# PM3_Bosclone_MCU_2.net
KiCad netlist of a schematic drawn in Altium Designer
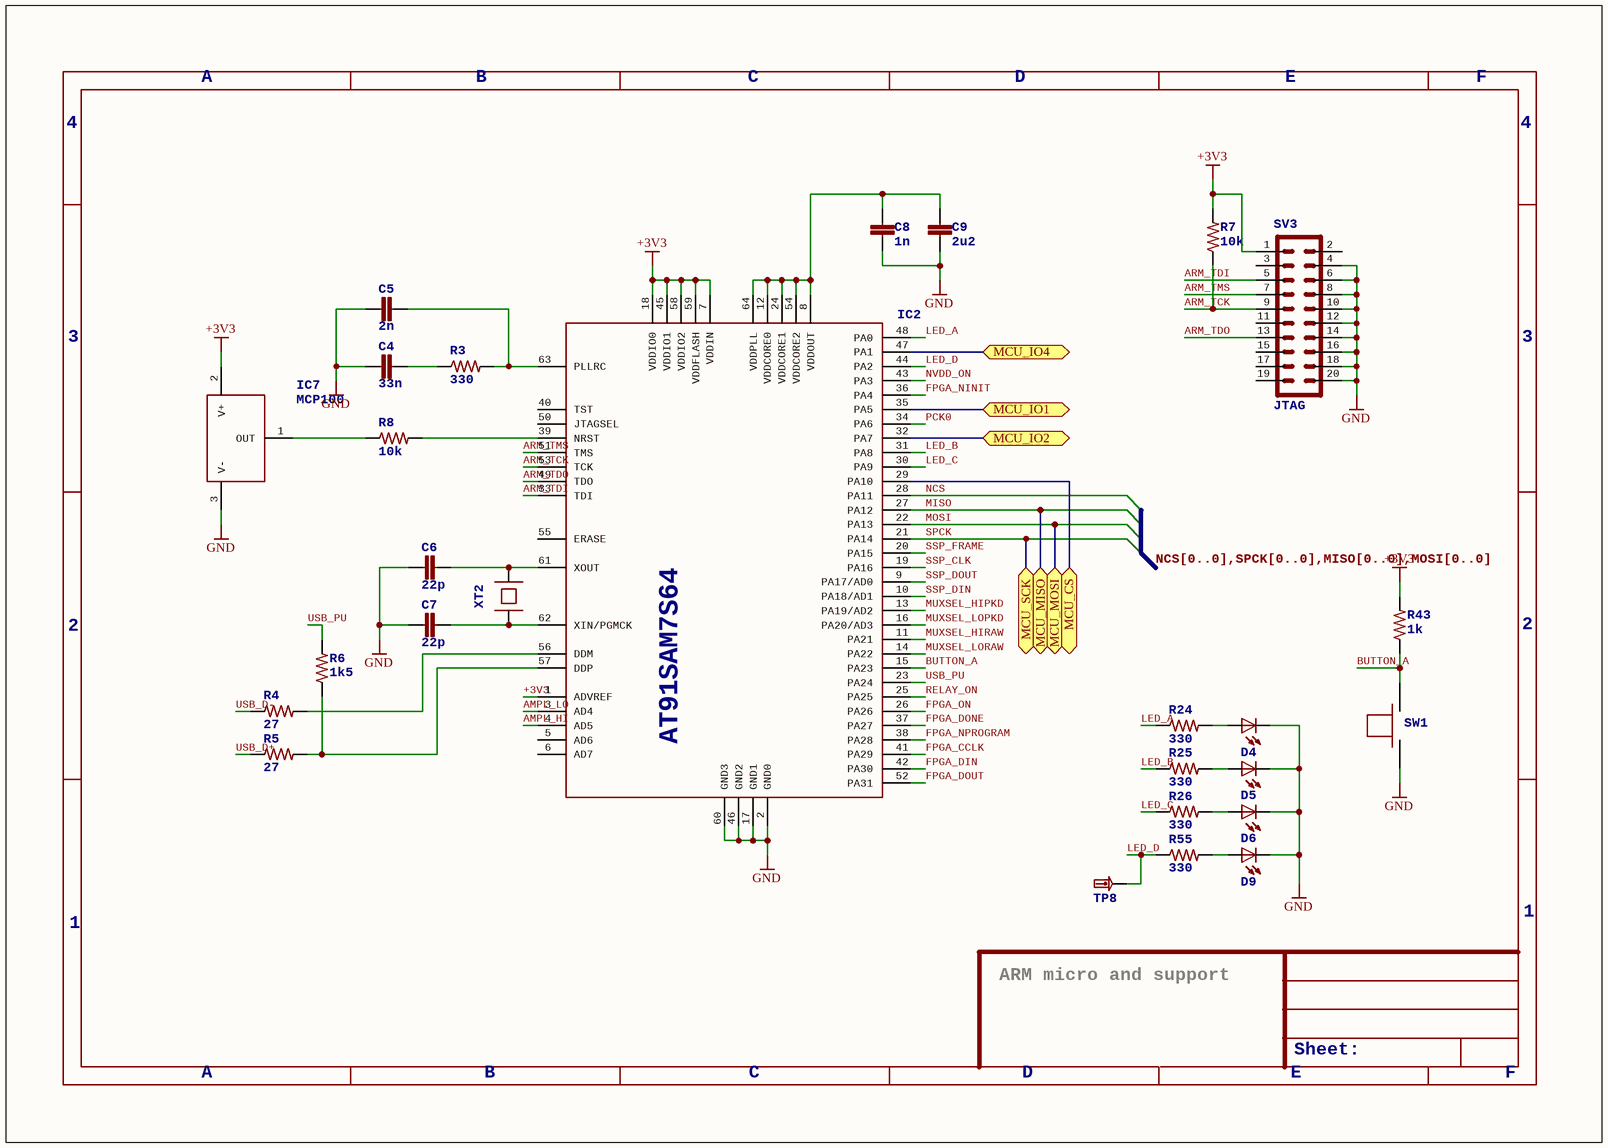
[diagram p0: PM3_Bosclone_MCU_2.SchDoc]

(export (version "E")
  (design (tool "Eeschema 10.0.6"))
  (components
    (comp (ref "C4") (value "33n") (footprint "RLC_0603") (libsource (lib "merged") (part "CAPACITOR0603")))
    (comp (ref "C5") (value "2n") (footprint "RLC_0603") (libsource (lib "merged") (part "CAPACITOR0603")))
    (comp (ref "C6") (value "22p") (footprint "RLC_0603") (libsource (lib "merged") (part "CAPACITOR0603")))
    (comp (ref "C7") (value "22p") (footprint "RLC_0603") (libsource (lib "merged") (part "CAPACITOR0603")))
    (comp (ref "C8") (value "1n") (footprint "RLC_0603") (libsource (lib "") (part "CAPACITOR0603_1")))
    (comp (ref "C9") (value "2u2") (footprint "RLC_1210") (libsource (lib "merged") (part "CAPACITOR1210")))
    (comp (ref "D4") (value "LED") (footprint "LED_0603") (libsource (lib "merged") (part "LED")))
    (comp (ref "D5") (value "LED") (footprint "LED_0603") (libsource (lib "merged") (part "LED")))
    (comp (ref "D6") (value "LED") (footprint "LED_0603") (libsource (lib "merged") (part "LED")))
    (comp (ref "D9") (value "LED") (footprint "LED_0603") (libsource (lib "merged") (part "LED")))
    (comp (ref "IC2")
      (value "AT91SAM7S64")
      (footprint "LQFP-64")
      (fields (field (name "AT91SAM7S64") "AT91SAM7S64"))
      (libsource (lib "merged") (part "AT91SAM7S64"))
    )
    (comp (ref "IC7") (value "MCP100") (footprint "SOT23-3LEAD") (libsource (lib "merged") (part "MCP100")))
    (comp (ref "R3") (value "330") (footprint "RLC_0603") (libsource (lib "merged") (part "RESISTOR0603")))
    (comp (ref "R4") (value "27") (footprint "RLC_0603") (libsource (lib "merged") (part "RESISTOR0603")))
    (comp (ref "R5") (value "27") (footprint "RLC_0603") (libsource (lib "merged") (part "RESISTOR0603")))
    (comp (ref "R6") (value "1k5") (footprint "RLC_0603") (libsource (lib "merged") (part "RESISTOR0603")))
    (comp (ref "R7") (value "10k") (footprint "RLC_0603") (libsource (lib "merged") (part "RESISTOR0603")))
    (comp (ref "R8") (value "10k") (footprint "RLC_0603") (libsource (lib "merged") (part "RESISTOR0603")))
    (comp (ref "R24") (value "330") (footprint "RLC_0603") (libsource (lib "merged") (part "RESISTOR0603")))
    (comp (ref "R25") (value "330") (footprint "RLC_0603") (libsource (lib "merged") (part "RESISTOR0603")))
    (comp (ref "R26") (value "330") (footprint "RLC_0603") (libsource (lib "merged") (part "RESISTOR0603")))
    (comp (ref "R43") (value "1k") (footprint "RLC_0603") (libsource (lib "merged") (part "RESISTOR0603")))
    (comp (ref "R55") (value "330") (footprint "RLC_0603") (libsource (lib "merged") (part "RESISTOR0603")))
    (comp (ref "SV3")
      (value "JTAG")
      (footprint "HEADER-MALE-10X2-0.100-SHROUDED")
      (libsource (lib "merged") (part "HEADER-MALE-10X2"))
    )
    (comp (ref "SW1")
      (value "TACTSWITCH")
      (footprint "TACTSWITCH-SMD-EVQQ1")
      (libsource (lib "merged") (part "TACTSWITCH"))
    )
    (comp (ref "TP8")
      (value "TESTPADKEYSTONE-SMD")
      (footprint "KEYSTONE-SMD-TESTPOINT-5015")
      (libsource (lib "merged") (part "TESTPADKEYSTONE-SMD"))
    )
    (comp (ref "XT2")
      (value "XTAL-SMD-CITIZEN-CS10")
      (footprint "XTAL-SMD-CITIZEN-CS10")
      (libsource (lib "merged") (part "XTAL-SMD-CITIZEN-CS10"))
    )
  )
  (nets
    (net (code "2") (name "+3V3") (class "Default")
      (node (ref "IC2") (pin "1") (pinfunction "ADVREF_1") (pintype "passive"))
      (node (ref "IC2") (pin "18") (pinfunction "VDDIO0_18") (pintype "passive"))
      (node (ref "IC2") (pin "45") (pinfunction "VDDIO1_45") (pintype "passive"))
      (node (ref "IC2") (pin "58") (pinfunction "VDDIO2_58") (pintype "passive"))
      (node (ref "IC2") (pin "59") (pinfunction "VDDFLASH_59") (pintype "passive"))
      (node (ref "IC2") (pin "7") (pinfunction "VDDIN_7") (pintype "passive"))
      (node (ref "IC7") (pin "2") (pinfunction "V+_2") (pintype "passive"))
      (node (ref "R43") (pin "2") (pinfunction "2_2") (pintype "passive"))
      (node (ref "R7") (pin "2") (pinfunction "2_2") (pintype "passive"))
      (node (ref "SV3") (pin "1") (pinfunction "1_1") (pintype "passive"))
    )
    (net (code "3") (name "/AMPL_HI") (class "Default")
      (node (ref "IC2") (pin "4") (pinfunction "AD5_4") (pintype "passive"))
    )
    (net (code "4") (name "/AMPL_LO") (class "Default")
      (node (ref "IC2") (pin "3") (pinfunction "AD4_3") (pintype "passive"))
    )
    (net (code "5") (name "/ARM_TCK") (class "Default")
      (node (ref "IC2") (pin "53") (pinfunction "TCK_53") (pintype "passive"))
      (node (ref "R7") (pin "1") (pinfunction "1_1") (pintype "passive"))
      (node (ref "SV3") (pin "9") (pinfunction "9_9") (pintype "passive"))
    )
    (net (code "6") (name "/ARM_TDI") (class "Default")
      (node (ref "IC2") (pin "33") (pinfunction "TDI_33") (pintype "passive"))
      (node (ref "SV3") (pin "5") (pinfunction "5_5") (pintype "passive"))
    )
    (net (code "7") (name "/ARM_TDO") (class "Default")
      (node (ref "IC2") (pin "49") (pinfunction "TDO_49") (pintype "passive"))
      (node (ref "SV3") (pin "13") (pinfunction "13_13") (pintype "passive"))
    )
    (net (code "8") (name "/ARM_TMS") (class "Default")
      (node (ref "IC2") (pin "51") (pinfunction "TMS_51") (pintype "passive"))
      (node (ref "SV3") (pin "7") (pinfunction "7_7") (pintype "passive"))
    )
    (net (code "9") (name "/BUTTON_A") (class "Default")
      (node (ref "IC2") (pin "15") (pinfunction "PA23_15") (pintype "passive"))
      (node (ref "R43") (pin "1") (pinfunction "1_1") (pintype "passive"))
      (node (ref "SW1") (pin "B") (pinfunction "P$2_B") (pintype "passive"))
    )
    (net (code "10") (name "/FPGA_CCLK") (class "Default")
      (node (ref "IC2") (pin "41") (pinfunction "PA29_41") (pintype "passive"))
    )
    (net (code "11") (name "/FPGA_DIN") (class "Default")
      (node (ref "IC2") (pin "42") (pinfunction "PA30_42") (pintype "passive"))
    )
    (net (code "12") (name "/FPGA_DONE") (class "Default")
      (node (ref "IC2") (pin "37") (pinfunction "PA27_37") (pintype "passive"))
    )
    (net (code "13") (name "/FPGA_DOUT") (class "Default")
      (node (ref "IC2") (pin "52") (pinfunction "PA31_52") (pintype "passive"))
    )
    (net (code "14") (name "/FPGA_NINIT") (class "Default")
      (node (ref "IC2") (pin "36") (pinfunction "PA4_36") (pintype "passive"))
    )
    (net (code "15") (name "/FPGA_NPROGRAM") (class "Default")
      (node (ref "IC2") (pin "38") (pinfunction "PA28_38") (pintype "passive"))
    )
    (net (code "16") (name "/FPGA_ON") (class "Default")
      (node (ref "IC2") (pin "26") (pinfunction "PA26_26") (pintype "passive"))
    )
    (net (code "17") (name "/LED_A") (class "Default")
      (node (ref "IC2") (pin "48") (pinfunction "PA0_48") (pintype "passive"))
      (node (ref "R24") (pin "1") (pinfunction "1_1") (pintype "passive"))
    )
    (net (code "18") (name "/LED_B") (class "Default")
      (node (ref "IC2") (pin "31") (pinfunction "PA8_31") (pintype "passive"))
      (node (ref "R25") (pin "1") (pinfunction "1_1") (pintype "passive"))
    )
    (net (code "19") (name "/LED_C") (class "Default")
      (node (ref "IC2") (pin "30") (pinfunction "PA9_30") (pintype "passive"))
      (node (ref "R26") (pin "1") (pinfunction "1_1") (pintype "passive"))
    )
    (net (code "20") (name "/LED_D") (class "Default")
      (node (ref "IC2") (pin "44") (pinfunction "PA2_44") (pintype "passive"))
      (node (ref "R55") (pin "1") (pinfunction "1_1") (pintype "passive"))
      (node (ref "TP8") (pin "1") (pinfunction "P$1_1") (pintype "passive"))
    )
    (net (code "21") (name "/MCU_CS") (class "Default")
      (node (ref "IC2") (pin "29") (pinfunction "PA10_29") (pintype "passive"))
    )
    (net (code "22") (name "/MCU_IO1") (class "Default")
      (node (ref "IC2") (pin "35") (pinfunction "PA5_35") (pintype "passive"))
    )
    (net (code "23") (name "/MCU_IO2") (class "Default")
      (node (ref "IC2") (pin "32") (pinfunction "PA7_32") (pintype "passive"))
    )
    (net (code "24") (name "/MCU_IO4") (class "Default")
      (node (ref "IC2") (pin "47") (pinfunction "PA1_47") (pintype "passive"))
    )
    (net (code "25") (name "/MISO") (class "Default")
      (node (ref "IC2") (pin "27") (pinfunction "PA12_27") (pintype "passive"))
    )
    (net (code "26") (name "/MOSI") (class "Default")
      (node (ref "IC2") (pin "22") (pinfunction "PA13_22") (pintype "passive"))
    )
    (net (code "27") (name "/MUXSEL_HIPKD") (class "Default")
      (node (ref "IC2") (pin "13") (pinfunction "PA19/AD2_13") (pintype "passive"))
    )
    (net (code "28") (name "/MUXSEL_HIRAW") (class "Default")
      (node (ref "IC2") (pin "11") (pinfunction "PA21_11") (pintype "passive"))
    )
    (net (code "29") (name "/MUXSEL_LOPKD") (class "Default")
      (node (ref "IC2") (pin "16") (pinfunction "PA20/AD3_16") (pintype "passive"))
    )
    (net (code "30") (name "/MUXSEL_LORAW") (class "Default")
      (node (ref "IC2") (pin "14") (pinfunction "PA22_14") (pintype "passive"))
    )
    (net (code "31") (name "/NCS") (class "Default")
      (node (ref "IC2") (pin "28") (pinfunction "PA11_28") (pintype "passive"))
    )
    (net (code "32") (name "/NVDD_ON") (class "Default")
      (node (ref "IC2") (pin "43") (pinfunction "PA3_43") (pintype "passive"))
    )
    (net (code "33") (name "/PCK0") (class "Default")
      (node (ref "IC2") (pin "34") (pinfunction "PA6_34") (pintype "passive"))
    )
    (net (code "34") (name "/RELAY_ON") (class "Default")
      (node (ref "IC2") (pin "25") (pinfunction "PA25_25") (pintype "passive"))
    )
    (net (code "35") (name "/SPCK") (class "Default")
      (node (ref "IC2") (pin "21") (pinfunction "PA14_21") (pintype "passive"))
    )
    (net (code "36") (name "/SSP_CLK") (class "Default")
      (node (ref "IC2") (pin "19") (pinfunction "PA16_19") (pintype "passive"))
    )
    (net (code "37") (name "/SSP_DIN") (class "Default")
      (node (ref "IC2") (pin "10") (pinfunction "PA18/AD1_10") (pintype "passive"))
    )
    (net (code "38") (name "/SSP_DOUT") (class "Default")
      (node (ref "IC2") (pin "9") (pinfunction "PA17/AD0_9") (pintype "passive"))
    )
    (net (code "39") (name "/SSP_FRAME") (class "Default")
      (node (ref "IC2") (pin "20") (pinfunction "PA15_20") (pintype "passive"))
    )
    (net (code "40") (name "/USB_D+") (class "Default")
      (node (ref "R5") (pin "1") (pinfunction "1_1") (pintype "passive"))
    )
    (net (code "41") (name "/USB_D-") (class "Default")
      (node (ref "R4") (pin "1") (pinfunction "1_1") (pintype "passive"))
    )
    (net (code "42") (name "/USB_PU") (class "Default")
      (node (ref "IC2") (pin "23") (pinfunction "PA24_23") (pintype "passive"))
      (node (ref "R6") (pin "2") (pinfunction "2_2") (pintype "passive"))
    )
    (net (code "44") (name "GND") (class "Default")
      (node (ref "C4") (pin "1") (pinfunction "1_1") (pintype "passive"))
      (node (ref "C5") (pin "1") (pinfunction "1_1") (pintype "passive"))
      (node (ref "C6") (pin "1") (pinfunction "1_1") (pintype "passive"))
      (node (ref "C7") (pin "1") (pinfunction "1_1") (pintype "passive"))
      (node (ref "C8") (pin "2") (pinfunction "2_2") (pintype "passive"))
      (node (ref "C9") (pin "2") (pinfunction "2_2") (pintype "passive"))
      (node (ref "D4") (pin "-") (pinfunction "C_-") (pintype "passive"))
      (node (ref "D5") (pin "-") (pinfunction "C_-") (pintype "passive"))
      (node (ref "D6") (pin "-") (pinfunction "C_-") (pintype "passive"))
      (node (ref "D9") (pin "-") (pinfunction "C_-") (pintype "passive"))
      (node (ref "IC2") (pin "17") (pinfunction "GND1_17") (pintype "passive"))
      (node (ref "IC2") (pin "2") (pinfunction "GND0_2") (pintype "passive"))
      (node (ref "IC2") (pin "46") (pinfunction "GND2_46") (pintype "passive"))
      (node (ref "IC2") (pin "60") (pinfunction "GND3_60") (pintype "passive"))
      (node (ref "IC7") (pin "3") (pinfunction "V-_3") (pintype "passive"))
      (node (ref "SV3") (pin "10") (pinfunction "10_10") (pintype "passive"))
      (node (ref "SV3") (pin "12") (pinfunction "12_12") (pintype "passive"))
      (node (ref "SV3") (pin "14") (pinfunction "14_14") (pintype "passive"))
      (node (ref "SV3") (pin "16") (pinfunction "16_16") (pintype "passive"))
      (node (ref "SV3") (pin "18") (pinfunction "18_18") (pintype "passive"))
      (node (ref "SV3") (pin "20") (pinfunction "20_20") (pintype "passive"))
      (node (ref "SV3") (pin "4") (pinfunction "4_4") (pintype "passive"))
      (node (ref "SV3") (pin "6") (pinfunction "6_6") (pintype "passive"))
      (node (ref "SV3") (pin "8") (pinfunction "8_8") (pintype "passive"))
      (node (ref "SW1") (pin "A") (pinfunction "P$1_A") (pintype "passive"))
    )
    (net (code "45") (name "Net-(C4-Pad2)") (class "Default")
      (node (ref "C4") (pin "2") (pinfunction "2_2") (pintype "passive"))
      (node (ref "R3") (pin "1") (pinfunction "1_1") (pintype "passive"))
    )
    (net (code "46") (name "Net-(D4-A)") (class "Default")
      (node (ref "D4") (pin "+") (pinfunction "A_+") (pintype "passive"))
      (node (ref "R24") (pin "2") (pinfunction "2_2") (pintype "passive"))
    )
    (net (code "47") (name "Net-(D5-A)") (class "Default")
      (node (ref "D5") (pin "+") (pinfunction "A_+") (pintype "passive"))
      (node (ref "R25") (pin "2") (pinfunction "2_2") (pintype "passive"))
    )
    (net (code "48") (name "Net-(D6-A)") (class "Default")
      (node (ref "D6") (pin "+") (pinfunction "A_+") (pintype "passive"))
      (node (ref "R26") (pin "2") (pinfunction "2_2") (pintype "passive"))
    )
    (net (code "49") (name "Net-(D9-A)") (class "Default")
      (node (ref "D9") (pin "+") (pinfunction "A_+") (pintype "passive"))
      (node (ref "R55") (pin "2") (pinfunction "2_2") (pintype "passive"))
    )
    (net (code "50") (name "Net-(IC2-DDM)") (class "Default")
      (node (ref "IC2") (pin "56") (pinfunction "DDM_56") (pintype "passive"))
      (node (ref "R4") (pin "2") (pinfunction "2_2") (pintype "passive"))
    )
    (net (code "51") (name "Net-(IC2-DDP)") (class "Default")
      (node (ref "IC2") (pin "57") (pinfunction "DDP_57") (pintype "passive"))
      (node (ref "R5") (pin "2") (pinfunction "2_2") (pintype "passive"))
      (node (ref "R6") (pin "1") (pinfunction "1_1") (pintype "passive"))
    )
    (net (code "52") (name "Net-(IC2-NRST)") (class "Default")
      (node (ref "IC2") (pin "39") (pinfunction "NRST_39") (pintype "passive"))
      (node (ref "R8") (pin "2") (pinfunction "2_2") (pintype "passive"))
    )
    (net (code "53") (name "Net-(IC2-PLLRC)") (class "Default")
      (node (ref "C5") (pin "2") (pinfunction "2_2") (pintype "passive"))
      (node (ref "IC2") (pin "63") (pinfunction "PLLRC_63") (pintype "passive"))
      (node (ref "R3") (pin "2") (pinfunction "2_2") (pintype "passive"))
    )
    (net (code "54") (name "Net-(IC2-VDDCORE0)") (class "Default")
      (node (ref "C8") (pin "1") (pinfunction "1_1") (pintype "passive"))
      (node (ref "C9") (pin "1") (pinfunction "1_1") (pintype "passive"))
      (node (ref "IC2") (pin "12") (pinfunction "VDDCORE0_12") (pintype "passive"))
      (node (ref "IC2") (pin "24") (pinfunction "VDDCORE1_24") (pintype "passive"))
      (node (ref "IC2") (pin "54") (pinfunction "VDDCORE2_54") (pintype "passive"))
      (node (ref "IC2") (pin "64") (pinfunction "VDDPLL_64") (pintype "passive"))
      (node (ref "IC2") (pin "8") (pinfunction "VDDOUT_8") (pintype "passive"))
    )
    (net (code "55") (name "Net-(IC2-XIN{slash}PGMCK)") (class "Default")
      (node (ref "C7") (pin "2") (pinfunction "2_2") (pintype "passive"))
      (node (ref "IC2") (pin "62") (pinfunction "XIN/PGMCK_62") (pintype "passive"))
      (node (ref "XT2") (pin "A") (pinfunction "A_A") (pintype "passive"))
    )
    (net (code "56") (name "Net-(IC2-XOUT)") (class "Default")
      (node (ref "C6") (pin "2") (pinfunction "2_2") (pintype "passive"))
      (node (ref "IC2") (pin "61") (pinfunction "XOUT_61") (pintype "passive"))
      (node (ref "XT2") (pin "B") (pinfunction "B_B") (pintype "passive"))
    )
    (net (code "57") (name "Net-(IC7-OUT)") (class "Default")
      (node (ref "IC7") (pin "1") (pinfunction "OUT_1") (pintype "passive"))
      (node (ref "R8") (pin "1") (pinfunction "1_1") (pintype "passive"))
    )
    (net (code "58") (name "unconnected-(IC2-AD6-Pad5)") (class "Default")
      (node (ref "IC2") (pin "5") (pinfunction "AD6_5") (pintype "passive"))
    )
    (net (code "59") (name "unconnected-(IC2-AD7-Pad6)") (class "Default")
      (node (ref "IC2") (pin "6") (pinfunction "AD7_6") (pintype "passive"))
    )
    (net (code "60") (name "unconnected-(IC2-ERASE-Pad55)") (class "Default")
      (node (ref "IC2") (pin "55") (pinfunction "ERASE_55") (pintype "passive"))
    )
    (net (code "61") (name "unconnected-(IC2-JTAGSEL-Pad50)") (class "Default")
      (node (ref "IC2") (pin "50") (pinfunction "JTAGSEL_50") (pintype "passive"))
    )
    (net (code "62") (name "unconnected-(IC2-TST-Pad40)") (class "Default")
      (node (ref "IC2") (pin "40") (pinfunction "TST_40") (pintype "passive"))
    )
    (net (code "63") (name "unconnected-(SV3-Pad2)") (class "Default")
      (node (ref "SV3") (pin "2") (pinfunction "2_2") (pintype "passive"))
    )
    (net (code "64") (name "unconnected-(SV3-Pad3)") (class "Default")
      (node (ref "SV3") (pin "3") (pinfunction "3_3") (pintype "passive"))
    )
    (net (code "65") (name "unconnected-(SV3-Pad11)") (class "Default")
      (node (ref "SV3") (pin "11") (pinfunction "11_11") (pintype "passive"))
    )
    (net (code "66") (name "unconnected-(SV3-Pad15)") (class "Default")
      (node (ref "SV3") (pin "15") (pinfunction "15_15") (pintype "passive"))
    )
    (net (code "67") (name "unconnected-(SV3-Pad17)") (class "Default")
      (node (ref "SV3") (pin "17") (pinfunction "17_17") (pintype "passive"))
    )
    (net (code "68") (name "unconnected-(SV3-Pad19)") (class "Default")
      (node (ref "SV3") (pin "19") (pinfunction "19_19") (pintype "passive"))
    )
  )
)
